# SCH_RGB_LED_stick_th_2022-01-01.net
KiCad netlist of a schematic drawn in EasyEDA
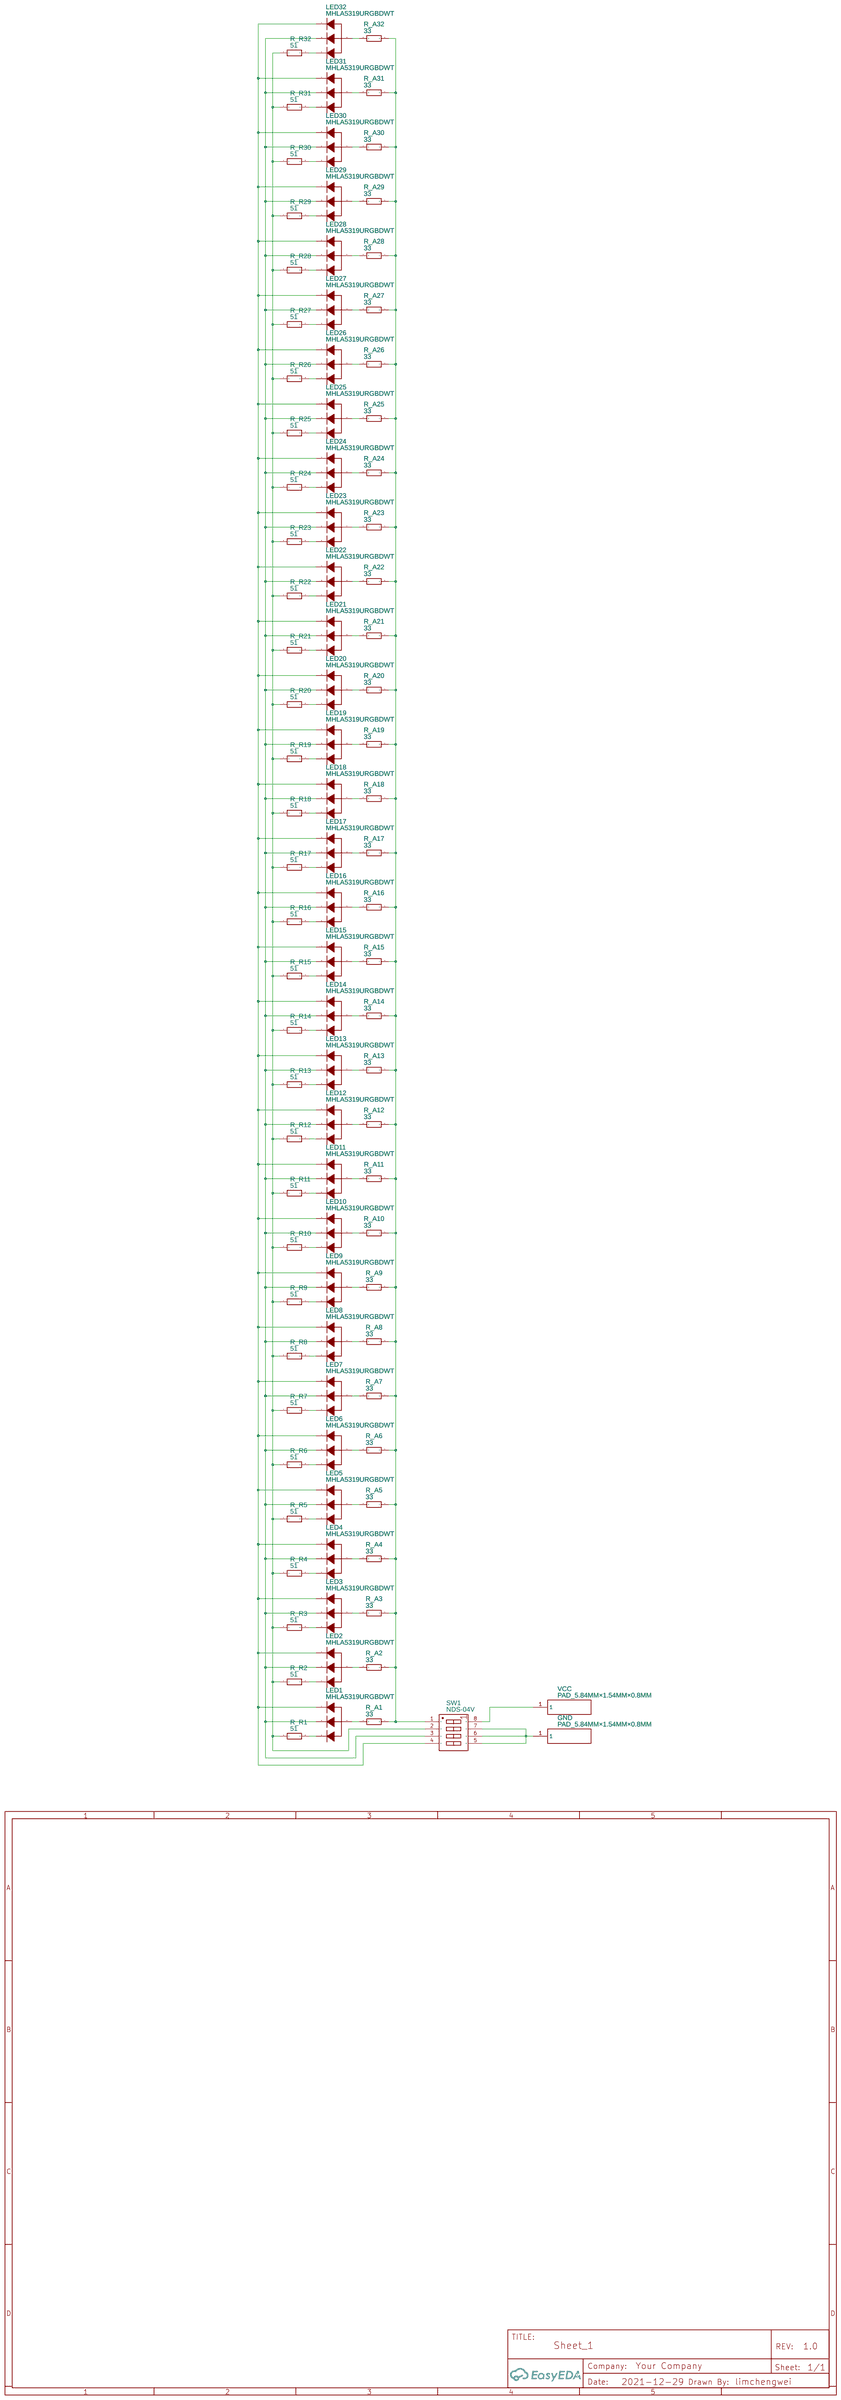
[diagram p0: schematic sheet]

(export (version "E")
  (design (tool "Eeschema 10.0.6"))
  (components
    (comp (ref "GND")
      (value "PAD_5.84MM×1.54MM×0.8MM")
      (fields
        (field (name "BOM_Manufacturer Part") "PAD_5.84mm×1.54mm×0.8mm")
        (field (name "BOM_Supplier Part") "C9900000335")
      )
      (libsource (lib "") (part "PAD_5.84MM×1.54MM×0.8MM"))
    )
    (comp (ref "LED1")
      (value "MHLA5319URGBDWT")
      (fields (field (name "BOM_Supplier Part") "C417349"))
      (libsource (lib "") (part "MHLA5319URGBDWT"))
    )
    (comp (ref "LED2")
      (value "MHLA5319URGBDWT")
      (fields (field (name "BOM_Supplier Part") "C417349"))
      (libsource (lib "") (part "MHLA5319URGBDWT"))
    )
    (comp (ref "LED3")
      (value "MHLA5319URGBDWT")
      (fields (field (name "BOM_Supplier Part") "C417349"))
      (libsource (lib "") (part "MHLA5319URGBDWT"))
    )
    (comp (ref "LED4")
      (value "MHLA5319URGBDWT")
      (fields (field (name "BOM_Supplier Part") "C417349"))
      (libsource (lib "") (part "MHLA5319URGBDWT"))
    )
    (comp (ref "LED5")
      (value "MHLA5319URGBDWT")
      (fields (field (name "BOM_Supplier Part") "C417349"))
      (libsource (lib "") (part "MHLA5319URGBDWT"))
    )
    (comp (ref "LED6")
      (value "MHLA5319URGBDWT")
      (fields (field (name "BOM_Supplier Part") "C417349"))
      (libsource (lib "") (part "MHLA5319URGBDWT"))
    )
    (comp (ref "LED7")
      (value "MHLA5319URGBDWT")
      (fields (field (name "BOM_Supplier Part") "C417349"))
      (libsource (lib "") (part "MHLA5319URGBDWT"))
    )
    (comp (ref "LED8")
      (value "MHLA5319URGBDWT")
      (fields (field (name "BOM_Supplier Part") "C417349"))
      (libsource (lib "") (part "MHLA5319URGBDWT"))
    )
    (comp (ref "LED9")
      (value "MHLA5319URGBDWT")
      (fields (field (name "BOM_Supplier Part") "C417349"))
      (libsource (lib "") (part "MHLA5319URGBDWT"))
    )
    (comp (ref "LED10")
      (value "MHLA5319URGBDWT")
      (fields (field (name "BOM_Supplier Part") "C417349"))
      (libsource (lib "") (part "MHLA5319URGBDWT"))
    )
    (comp (ref "LED11")
      (value "MHLA5319URGBDWT")
      (fields (field (name "BOM_Supplier Part") "C417349"))
      (libsource (lib "") (part "MHLA5319URGBDWT"))
    )
    (comp (ref "LED12")
      (value "MHLA5319URGBDWT")
      (fields (field (name "BOM_Supplier Part") "C417349"))
      (libsource (lib "") (part "MHLA5319URGBDWT"))
    )
    (comp (ref "LED13")
      (value "MHLA5319URGBDWT")
      (fields (field (name "BOM_Supplier Part") "C417349"))
      (libsource (lib "") (part "MHLA5319URGBDWT"))
    )
    (comp (ref "LED14")
      (value "MHLA5319URGBDWT")
      (fields (field (name "BOM_Supplier Part") "C417349"))
      (libsource (lib "") (part "MHLA5319URGBDWT"))
    )
    (comp (ref "LED15")
      (value "MHLA5319URGBDWT")
      (fields (field (name "BOM_Supplier Part") "C417349"))
      (libsource (lib "") (part "MHLA5319URGBDWT"))
    )
    (comp (ref "LED16")
      (value "MHLA5319URGBDWT")
      (fields (field (name "BOM_Supplier Part") "C417349"))
      (libsource (lib "") (part "MHLA5319URGBDWT"))
    )
    (comp (ref "LED17")
      (value "MHLA5319URGBDWT")
      (fields (field (name "BOM_Supplier Part") "C417349"))
      (libsource (lib "") (part "MHLA5319URGBDWT"))
    )
    (comp (ref "LED18")
      (value "MHLA5319URGBDWT")
      (fields (field (name "BOM_Supplier Part") "C417349"))
      (libsource (lib "") (part "MHLA5319URGBDWT"))
    )
    (comp (ref "LED19")
      (value "MHLA5319URGBDWT")
      (fields (field (name "BOM_Supplier Part") "C417349"))
      (libsource (lib "") (part "MHLA5319URGBDWT"))
    )
    (comp (ref "LED20")
      (value "MHLA5319URGBDWT")
      (fields (field (name "BOM_Supplier Part") "C417349"))
      (libsource (lib "") (part "MHLA5319URGBDWT"))
    )
    (comp (ref "LED21")
      (value "MHLA5319URGBDWT")
      (fields (field (name "BOM_Supplier Part") "C417349"))
      (libsource (lib "") (part "MHLA5319URGBDWT"))
    )
    (comp (ref "LED22")
      (value "MHLA5319URGBDWT")
      (fields (field (name "BOM_Supplier Part") "C417349"))
      (libsource (lib "") (part "MHLA5319URGBDWT"))
    )
    (comp (ref "LED23")
      (value "MHLA5319URGBDWT")
      (fields (field (name "BOM_Supplier Part") "C417349"))
      (libsource (lib "") (part "MHLA5319URGBDWT"))
    )
    (comp (ref "LED24")
      (value "MHLA5319URGBDWT")
      (fields (field (name "BOM_Supplier Part") "C417349"))
      (libsource (lib "") (part "MHLA5319URGBDWT"))
    )
    (comp (ref "LED25")
      (value "MHLA5319URGBDWT")
      (fields (field (name "BOM_Supplier Part") "C417349"))
      (libsource (lib "") (part "MHLA5319URGBDWT"))
    )
    (comp (ref "LED26")
      (value "MHLA5319URGBDWT")
      (fields (field (name "BOM_Supplier Part") "C417349"))
      (libsource (lib "") (part "MHLA5319URGBDWT"))
    )
    (comp (ref "LED27")
      (value "MHLA5319URGBDWT")
      (fields (field (name "BOM_Supplier Part") "C417349"))
      (libsource (lib "") (part "MHLA5319URGBDWT"))
    )
    (comp (ref "LED28")
      (value "MHLA5319URGBDWT")
      (fields (field (name "BOM_Supplier Part") "C417349"))
      (libsource (lib "") (part "MHLA5319URGBDWT"))
    )
    (comp (ref "LED29")
      (value "MHLA5319URGBDWT")
      (fields (field (name "BOM_Supplier Part") "C417349"))
      (libsource (lib "") (part "MHLA5319URGBDWT"))
    )
    (comp (ref "LED30")
      (value "MHLA5319URGBDWT")
      (fields (field (name "BOM_Supplier Part") "C417349"))
      (libsource (lib "") (part "MHLA5319URGBDWT"))
    )
    (comp (ref "LED31")
      (value "MHLA5319URGBDWT")
      (fields (field (name "BOM_Supplier Part") "C417349"))
      (libsource (lib "") (part "MHLA5319URGBDWT"))
    )
    (comp (ref "LED32")
      (value "MHLA5319URGBDWT")
      (fields (field (name "BOM_Supplier Part") "C417349"))
      (libsource (lib "") (part "MHLA5319URGBDWT"))
    )
    (comp (ref "R_A1")
      (value "33")
      (fields (field (name "BOM_Supplier Part") "C119319"))
      (libsource (lib "") (part "MF1/4W-620Ω±1% T52_1"))
    )
    (comp (ref "R_A2")
      (value "33")
      (fields (field (name "BOM_Supplier Part") "C119319"))
      (libsource (lib "") (part "MF1/4W-620Ω±1% T52_1"))
    )
    (comp (ref "R_A3")
      (value "33")
      (fields (field (name "BOM_Supplier Part") "C119319"))
      (libsource (lib "") (part "MF1/4W-620Ω±1% T52_1"))
    )
    (comp (ref "R_A4")
      (value "33")
      (fields (field (name "BOM_Supplier Part") "C119319"))
      (libsource (lib "") (part "MF1/4W-620Ω±1% T52_1"))
    )
    (comp (ref "R_A5")
      (value "33")
      (fields (field (name "BOM_Supplier Part") "C119319"))
      (libsource (lib "") (part "MF1/4W-620Ω±1% T52_1"))
    )
    (comp (ref "R_A6")
      (value "33")
      (fields (field (name "BOM_Supplier Part") "C119319"))
      (libsource (lib "") (part "MF1/4W-620Ω±1% T52_1"))
    )
    (comp (ref "R_A7")
      (value "33")
      (fields (field (name "BOM_Supplier Part") "C119319"))
      (libsource (lib "") (part "MF1/4W-620Ω±1% T52_1"))
    )
    (comp (ref "R_A8")
      (value "33")
      (fields (field (name "BOM_Supplier Part") "C119319"))
      (libsource (lib "") (part "MF1/4W-620Ω±1% T52_1"))
    )
    (comp (ref "R_A9")
      (value "33")
      (fields (field (name "BOM_Supplier Part") "C119319"))
      (libsource (lib "") (part "MF1/4W-620Ω±1% T52_1"))
    )
    (comp (ref "R_A10")
      (value "33")
      (fields (field (name "BOM_Supplier Part") "C119319"))
      (libsource (lib "") (part "MF1/4W-620Ω±1% T52_1"))
    )
    (comp (ref "R_A11")
      (value "33")
      (fields (field (name "BOM_Supplier Part") "C119319"))
      (libsource (lib "") (part "MF1/4W-620Ω±1% T52_1"))
    )
    (comp (ref "R_A12")
      (value "33")
      (fields (field (name "BOM_Supplier Part") "C119319"))
      (libsource (lib "") (part "MF1/4W-620Ω±1% T52_1"))
    )
    (comp (ref "R_A13")
      (value "33")
      (fields (field (name "BOM_Supplier Part") "C119319"))
      (libsource (lib "") (part "MF1/4W-620Ω±1% T52_1"))
    )
    (comp (ref "R_A14")
      (value "33")
      (fields (field (name "BOM_Supplier Part") "C119319"))
      (libsource (lib "") (part "MF1/4W-620Ω±1% T52_1"))
    )
    (comp (ref "R_A15")
      (value "33")
      (fields (field (name "BOM_Supplier Part") "C119319"))
      (libsource (lib "") (part "MF1/4W-620Ω±1% T52_1"))
    )
    (comp (ref "R_A16")
      (value "33")
      (fields (field (name "BOM_Supplier Part") "C119319"))
      (libsource (lib "") (part "MF1/4W-620Ω±1% T52_1"))
    )
    (comp (ref "R_A17")
      (value "33")
      (fields (field (name "BOM_Supplier Part") "C119319"))
      (libsource (lib "") (part "MF1/4W-620Ω±1% T52_1"))
    )
    (comp (ref "R_A18")
      (value "33")
      (fields (field (name "BOM_Supplier Part") "C119319"))
      (libsource (lib "") (part "MF1/4W-620Ω±1% T52_1"))
    )
    (comp (ref "R_A19")
      (value "33")
      (fields (field (name "BOM_Supplier Part") "C119319"))
      (libsource (lib "") (part "MF1/4W-620Ω±1% T52_1"))
    )
    (comp (ref "R_A20")
      (value "33")
      (fields (field (name "BOM_Supplier Part") "C119319"))
      (libsource (lib "") (part "MF1/4W-620Ω±1% T52_1"))
    )
    (comp (ref "R_A21")
      (value "33")
      (fields (field (name "BOM_Supplier Part") "C119319"))
      (libsource (lib "") (part "MF1/4W-620Ω±1% T52_1"))
    )
    (comp (ref "R_A22")
      (value "33")
      (fields (field (name "BOM_Supplier Part") "C119319"))
      (libsource (lib "") (part "MF1/4W-620Ω±1% T52_1"))
    )
    (comp (ref "R_A23")
      (value "33")
      (fields (field (name "BOM_Supplier Part") "C119319"))
      (libsource (lib "") (part "MF1/4W-620Ω±1% T52_1"))
    )
    (comp (ref "R_A24")
      (value "33")
      (fields (field (name "BOM_Supplier Part") "C119319"))
      (libsource (lib "") (part "MF1/4W-620Ω±1% T52_1"))
    )
    (comp (ref "R_A25")
      (value "33")
      (fields (field (name "BOM_Supplier Part") "C119319"))
      (libsource (lib "") (part "MF1/4W-620Ω±1% T52_1"))
    )
    (comp (ref "R_A26")
      (value "33")
      (fields (field (name "BOM_Supplier Part") "C119319"))
      (libsource (lib "") (part "MF1/4W-620Ω±1% T52_1"))
    )
    (comp (ref "R_A27")
      (value "33")
      (fields (field (name "BOM_Supplier Part") "C119319"))
      (libsource (lib "") (part "MF1/4W-620Ω±1% T52_1"))
    )
    (comp (ref "R_A28")
      (value "33")
      (fields (field (name "BOM_Supplier Part") "C119319"))
      (libsource (lib "") (part "MF1/4W-620Ω±1% T52_1"))
    )
    (comp (ref "R_A29")
      (value "33")
      (fields (field (name "BOM_Supplier Part") "C119319"))
      (libsource (lib "") (part "MF1/4W-620Ω±1% T52_1"))
    )
    (comp (ref "R_A30")
      (value "33")
      (fields (field (name "BOM_Supplier Part") "C119319"))
      (libsource (lib "") (part "MF1/4W-620Ω±1% T52_1"))
    )
    (comp (ref "R_A31")
      (value "33")
      (fields (field (name "BOM_Supplier Part") "C119319"))
      (libsource (lib "") (part "MF1/4W-620Ω±1% T52_1"))
    )
    (comp (ref "R_A32")
      (value "33")
      (fields (field (name "BOM_Supplier Part") "C119319"))
      (libsource (lib "") (part "MF1/4W-620Ω±1% T52_1"))
    )
    (comp (ref "R_R1")
      (value "51")
      (fields (field (name "BOM_Supplier Part") "C119319"))
      (libsource (lib "") (part "MF1/4W-620Ω±1% T52"))
    )
    (comp (ref "R_R2")
      (value "51")
      (fields (field (name "BOM_Supplier Part") "C119319"))
      (libsource (lib "") (part "MF1/4W-620Ω±1% T52"))
    )
    (comp (ref "R_R3")
      (value "51")
      (fields (field (name "BOM_Supplier Part") "C119319"))
      (libsource (lib "") (part "MF1/4W-620Ω±1% T52"))
    )
    (comp (ref "R_R4")
      (value "51")
      (fields (field (name "BOM_Supplier Part") "C119319"))
      (libsource (lib "") (part "MF1/4W-620Ω±1% T52"))
    )
    (comp (ref "R_R5")
      (value "51")
      (fields (field (name "BOM_Supplier Part") "C119319"))
      (libsource (lib "") (part "MF1/4W-620Ω±1% T52"))
    )
    (comp (ref "R_R6")
      (value "51")
      (fields (field (name "BOM_Supplier Part") "C119319"))
      (libsource (lib "") (part "MF1/4W-620Ω±1% T52"))
    )
    (comp (ref "R_R7")
      (value "51")
      (fields (field (name "BOM_Supplier Part") "C119319"))
      (libsource (lib "") (part "MF1/4W-620Ω±1% T52"))
    )
    (comp (ref "R_R8")
      (value "51")
      (fields (field (name "BOM_Supplier Part") "C119319"))
      (libsource (lib "") (part "MF1/4W-620Ω±1% T52"))
    )
    (comp (ref "R_R9")
      (value "51")
      (fields (field (name "BOM_Supplier Part") "C119319"))
      (libsource (lib "") (part "MF1/4W-620Ω±1% T52"))
    )
    (comp (ref "R_R10")
      (value "51")
      (fields (field (name "BOM_Supplier Part") "C119319"))
      (libsource (lib "") (part "MF1/4W-620Ω±1% T52"))
    )
    (comp (ref "R_R11")
      (value "51")
      (fields (field (name "BOM_Supplier Part") "C119319"))
      (libsource (lib "") (part "MF1/4W-620Ω±1% T52"))
    )
    (comp (ref "R_R12")
      (value "51")
      (fields (field (name "BOM_Supplier Part") "C119319"))
      (libsource (lib "") (part "MF1/4W-620Ω±1% T52"))
    )
    (comp (ref "R_R13")
      (value "51")
      (fields (field (name "BOM_Supplier Part") "C119319"))
      (libsource (lib "") (part "MF1/4W-620Ω±1% T52"))
    )
    (comp (ref "R_R14")
      (value "51")
      (fields (field (name "BOM_Supplier Part") "C119319"))
      (libsource (lib "") (part "MF1/4W-620Ω±1% T52"))
    )
    (comp (ref "R_R15")
      (value "51")
      (fields (field (name "BOM_Supplier Part") "C119319"))
      (libsource (lib "") (part "MF1/4W-620Ω±1% T52"))
    )
    (comp (ref "R_R16")
      (value "51")
      (fields (field (name "BOM_Supplier Part") "C119319"))
      (libsource (lib "") (part "MF1/4W-620Ω±1% T52"))
    )
    (comp (ref "R_R17")
      (value "51")
      (fields (field (name "BOM_Supplier Part") "C119319"))
      (libsource (lib "") (part "MF1/4W-620Ω±1% T52"))
    )
    (comp (ref "R_R18")
      (value "51")
      (fields (field (name "BOM_Supplier Part") "C119319"))
      (libsource (lib "") (part "MF1/4W-620Ω±1% T52"))
    )
    (comp (ref "R_R19")
      (value "51")
      (fields (field (name "BOM_Supplier Part") "C119319"))
      (libsource (lib "") (part "MF1/4W-620Ω±1% T52"))
    )
    (comp (ref "R_R20")
      (value "51")
      (fields (field (name "BOM_Supplier Part") "C119319"))
      (libsource (lib "") (part "MF1/4W-620Ω±1% T52"))
    )
    (comp (ref "R_R21")
      (value "51")
      (fields (field (name "BOM_Supplier Part") "C119319"))
      (libsource (lib "") (part "MF1/4W-620Ω±1% T52"))
    )
    (comp (ref "R_R22")
      (value "51")
      (fields (field (name "BOM_Supplier Part") "C119319"))
      (libsource (lib "") (part "MF1/4W-620Ω±1% T52"))
    )
    (comp (ref "R_R23")
      (value "51")
      (fields (field (name "BOM_Supplier Part") "C119319"))
      (libsource (lib "") (part "MF1/4W-620Ω±1% T52"))
    )
    (comp (ref "R_R24")
      (value "51")
      (fields (field (name "BOM_Supplier Part") "C119319"))
      (libsource (lib "") (part "MF1/4W-620Ω±1% T52"))
    )
    (comp (ref "R_R25")
      (value "51")
      (fields (field (name "BOM_Supplier Part") "C119319"))
      (libsource (lib "") (part "MF1/4W-620Ω±1% T52"))
    )
    (comp (ref "R_R26")
      (value "51")
      (fields (field (name "BOM_Supplier Part") "C119319"))
      (libsource (lib "") (part "MF1/4W-620Ω±1% T52"))
    )
    (comp (ref "R_R27")
      (value "51")
      (fields (field (name "BOM_Supplier Part") "C119319"))
      (libsource (lib "") (part "MF1/4W-620Ω±1% T52"))
    )
    (comp (ref "R_R28")
      (value "51")
      (fields (field (name "BOM_Supplier Part") "C119319"))
      (libsource (lib "") (part "MF1/4W-620Ω±1% T52"))
    )
    (comp (ref "R_R29")
      (value "51")
      (fields (field (name "BOM_Supplier Part") "C119319"))
      (libsource (lib "") (part "MF1/4W-620Ω±1% T52"))
    )
    (comp (ref "R_R30")
      (value "51")
      (fields (field (name "BOM_Supplier Part") "C119319"))
      (libsource (lib "") (part "MF1/4W-620Ω±1% T52"))
    )
    (comp (ref "R_R31")
      (value "51")
      (fields (field (name "BOM_Supplier Part") "C119319"))
      (libsource (lib "") (part "MF1/4W-620Ω±1% T52"))
    )
    (comp (ref "R_R32")
      (value "51")
      (fields (field (name "BOM_Supplier Part") "C119319"))
      (libsource (lib "") (part "MF1/4W-620Ω±1% T52"))
    )
    (comp (ref "SW1")
      (value "NDS-04V")
      (fields (field (name "BOM_Supplier Part") "C501536"))
      (libsource (lib "") (part "NDS-04V"))
    )
    (comp (ref "VCC")
      (value "PAD_5.84MM×1.54MM×0.8MM")
      (fields
        (field (name "BOM_Manufacturer Part") "PAD_5.84mm×1.54mm×0.8mm")
        (field (name "BOM_Supplier Part") "C9900000335")
      )
      (libsource (lib "") (part "PAD_5.84MM×1.54MM×0.8MM_1"))
    )
  )
  (nets
    (net (code "1") (name "Net-(LED1-+)") (class "Default")
      (node (ref "LED1") (pin "2") (pinfunction "+_2") (pintype "unspecified"))
      (node (ref "R_A1") (pin "2") (pinfunction "2_2") (pintype "unspecified"))
    )
    (net (code "2") (name "Net-(LED1---Pad1)") (class "Default")
      (node (ref "LED1") (pin "1") (pinfunction "-_1") (pintype "unspecified"))
      (node (ref "R_R1") (pin "2") (pinfunction "2_2") (pintype "unspecified"))
    )
    (net (code "3") (name "Net-(LED2-+)") (class "Default")
      (node (ref "LED2") (pin "2") (pinfunction "+_2") (pintype "unspecified"))
      (node (ref "R_A2") (pin "2") (pinfunction "2_2") (pintype "unspecified"))
    )
    (net (code "4") (name "Net-(LED2---Pad1)") (class "Default")
      (node (ref "LED2") (pin "1") (pinfunction "-_1") (pintype "unspecified"))
      (node (ref "R_R2") (pin "2") (pinfunction "2_2") (pintype "unspecified"))
    )
    (net (code "5") (name "Net-(LED3-+)") (class "Default")
      (node (ref "LED3") (pin "2") (pinfunction "+_2") (pintype "unspecified"))
      (node (ref "R_A3") (pin "2") (pinfunction "2_2") (pintype "unspecified"))
    )
    (net (code "6") (name "Net-(LED3---Pad1)") (class "Default")
      (node (ref "LED3") (pin "1") (pinfunction "-_1") (pintype "unspecified"))
      (node (ref "R_R3") (pin "2") (pinfunction "2_2") (pintype "unspecified"))
    )
    (net (code "7") (name "Net-(LED4-+)") (class "Default")
      (node (ref "LED4") (pin "2") (pinfunction "+_2") (pintype "unspecified"))
      (node (ref "R_A4") (pin "2") (pinfunction "2_2") (pintype "unspecified"))
    )
    (net (code "8") (name "Net-(LED4---Pad1)") (class "Default")
      (node (ref "LED4") (pin "1") (pinfunction "-_1") (pintype "unspecified"))
      (node (ref "R_R4") (pin "2") (pinfunction "2_2") (pintype "unspecified"))
    )
    (net (code "9") (name "Net-(LED5-+)") (class "Default")
      (node (ref "LED5") (pin "2") (pinfunction "+_2") (pintype "unspecified"))
      (node (ref "R_A5") (pin "2") (pinfunction "2_2") (pintype "unspecified"))
    )
    (net (code "10") (name "Net-(LED5---Pad1)") (class "Default")
      (node (ref "LED5") (pin "1") (pinfunction "-_1") (pintype "unspecified"))
      (node (ref "R_R5") (pin "2") (pinfunction "2_2") (pintype "unspecified"))
    )
    (net (code "11") (name "Net-(LED6-+)") (class "Default")
      (node (ref "LED6") (pin "2") (pinfunction "+_2") (pintype "unspecified"))
      (node (ref "R_A6") (pin "2") (pinfunction "2_2") (pintype "unspecified"))
    )
    (net (code "12") (name "Net-(LED6---Pad1)") (class "Default")
      (node (ref "LED6") (pin "1") (pinfunction "-_1") (pintype "unspecified"))
      (node (ref "R_R6") (pin "2") (pinfunction "2_2") (pintype "unspecified"))
    )
    (net (code "13") (name "Net-(LED7-+)") (class "Default")
      (node (ref "LED7") (pin "2") (pinfunction "+_2") (pintype "unspecified"))
      (node (ref "R_A7") (pin "2") (pinfunction "2_2") (pintype "unspecified"))
    )
    (net (code "14") (name "Net-(LED7---Pad1)") (class "Default")
      (node (ref "LED7") (pin "1") (pinfunction "-_1") (pintype "unspecified"))
      (node (ref "R_R7") (pin "2") (pinfunction "2_2") (pintype "unspecified"))
    )
    (net (code "15") (name "Net-(LED8-+)") (class "Default")
      (node (ref "LED8") (pin "2") (pinfunction "+_2") (pintype "unspecified"))
      (node (ref "R_A8") (pin "2") (pinfunction "2_2") (pintype "unspecified"))
    )
    (net (code "16") (name "Net-(LED8---Pad1)") (class "Default")
      (node (ref "LED8") (pin "1") (pinfunction "-_1") (pintype "unspecified"))
      (node (ref "R_R8") (pin "2") (pinfunction "2_2") (pintype "unspecified"))
    )
    (net (code "17") (name "Net-(LED9-+)") (class "Default")
      (node (ref "LED9") (pin "2") (pinfunction "+_2") (pintype "unspecified"))
      (node (ref "R_A9") (pin "2") (pinfunction "2_2") (pintype "unspecified"))
    )
    (net (code "18") (name "Net-(LED9---Pad1)") (class "Default")
      (node (ref "LED9") (pin "1") (pinfunction "-_1") (pintype "unspecified"))
      (node (ref "R_R9") (pin "2") (pinfunction "2_2") (pintype "unspecified"))
    )
    (net (code "19") (name "Net-(LED10-+)") (class "Default")
      (node (ref "LED10") (pin "2") (pinfunction "+_2") (pintype "unspecified"))
      (node (ref "R_A10") (pin "2") (pinfunction "2_2") (pintype "unspecified"))
    )
    (net (code "20") (name "Net-(LED10---Pad1)") (class "Default")
      (node (ref "LED10") (pin "1") (pinfunction "-_1") (pintype "unspecified"))
      (node (ref "R_R10") (pin "2") (pinfunction "2_2") (pintype "unspecified"))
    )
    (net (code "21") (name "Net-(LED11-+)") (class "Default")
      (node (ref "LED11") (pin "2") (pinfunction "+_2") (pintype "unspecified"))
      (node (ref "R_A11") (pin "2") (pinfunction "2_2") (pintype "unspecified"))
    )
    (net (code "22") (name "Net-(LED11---Pad1)") (class "Default")
      (node (ref "LED11") (pin "1") (pinfunction "-_1") (pintype "unspecified"))
      (node (ref "R_R11") (pin "2") (pinfunction "2_2") (pintype "unspecified"))
    )
    (net (code "23") (name "Net-(LED12-+)") (class "Default")
      (node (ref "LED12") (pin "2") (pinfunction "+_2") (pintype "unspecified"))
      (node (ref "R_A12") (pin "2") (pinfunction "2_2") (pintype "unspecified"))
    )
    (net (code "24") (name "Net-(LED12---Pad1)") (class "Default")
      (node (ref "LED12") (pin "1") (pinfunction "-_1") (pintype "unspecified"))
      (node (ref "R_R12") (pin "2") (pinfunction "2_2") (pintype "unspecified"))
    )
    (net (code "25") (name "Net-(LED13-+)") (class "Default")
      (node (ref "LED13") (pin "2") (pinfunction "+_2") (pintype "unspecified"))
      (node (ref "R_A13") (pin "2") (pinfunction "2_2") (pintype "unspecified"))
    )
    (net (code "26") (name "Net-(LED13---Pad1)") (class "Default")
      (node (ref "LED13") (pin "1") (pinfunction "-_1") (pintype "unspecified"))
      (node (ref "R_R13") (pin "2") (pinfunction "2_2") (pintype "unspecified"))
    )
    (net (code "27") (name "Net-(LED14-+)") (class "Default")
      (node (ref "LED14") (pin "2") (pinfunction "+_2") (pintype "unspecified"))
      (node (ref "R_A14") (pin "2") (pinfunction "2_2") (pintype "unspecified"))
    )
    (net (code "28") (name "Net-(LED14---Pad1)") (class "Default")
      (node (ref "LED14") (pin "1") (pinfunction "-_1") (pintype "unspecified"))
      (node (ref "R_R14") (pin "2") (pinfunction "2_2") (pintype "unspecified"))
    )
    (net (code "29") (name "Net-(LED15-+)") (class "Default")
      (node (ref "LED15") (pin "2") (pinfunction "+_2") (pintype "unspecified"))
      (node (ref "R_A15") (pin "2") (pinfunction "2_2") (pintype "unspecified"))
    )
    (net (code "30") (name "Net-(LED15---Pad1)") (class "Default")
      (node (ref "LED15") (pin "1") (pinfunction "-_1") (pintype "unspecified"))
      (node (ref "R_R15") (pin "2") (pinfunction "2_2") (pintype "unspecified"))
    )
    (net (code "31") (name "Net-(LED16-+)") (class "Default")
      (node (ref "LED16") (pin "2") (pinfunction "+_2") (pintype "unspecified"))
      (node (ref "R_A16") (pin "2") (pinfunction "2_2") (pintype "unspecified"))
    )
    (net (code "32") (name "Net-(LED16---Pad1)") (class "Default")
      (node (ref "LED16") (pin "1") (pinfunction "-_1") (pintype "unspecified"))
      (node (ref "R_R16") (pin "2") (pinfunction "2_2") (pintype "unspecified"))
    )
    (net (code "33") (name "Net-(LED17-+)") (class "Default")
      (node (ref "LED17") (pin "2") (pinfunction "+_2") (pintype "unspecified"))
      (node (ref "R_A17") (pin "2") (pinfunction "2_2") (pintype "unspecified"))
    )
    (net (code "34") (name "Net-(LED17---Pad1)") (class "Default")
      (node (ref "LED17") (pin "1") (pinfunction "-_1") (pintype "unspecified"))
      (node (ref "R_R17") (pin "2") (pinfunction "2_2") (pintype "unspecified"))
    )
    (net (code "35") (name "Net-(LED18-+)") (class "Default")
      (node (ref "LED18") (pin "2") (pinfunction "+_2") (pintype "unspecified"))
      (node (ref "R_A18") (pin "2") (pinfunction "2_2") (pintype "unspecified"))
    )
    (net (code "36") (name "Net-(LED18---Pad1)") (class "Default")
      (node (ref "LED18") (pin "1") (pinfunction "-_1") (pintype "unspecified"))
      (node (ref "R_R18") (pin "2") (pinfunction "2_2") (pintype "unspecified"))
    )
    (net (code "37") (name "Net-(LED19-+)") (class "Default")
      (node (ref "LED19") (pin "2") (pinfunction "+_2") (pintype "unspecified"))
      (node (ref "R_A19") (pin "2") (pinfunction "2_2") (pintype "unspecified"))
    )
    (net (code "38") (name "Net-(LED19---Pad1)") (class "Default")
      (node (ref "LED19") (pin "1") (pinfunction "-_1") (pintype "unspecified"))
      (node (ref "R_R19") (pin "2") (pinfunction "2_2") (pintype "unspecified"))
    )
    (net (code "39") (name "Net-(LED20-+)") (class "Default")
      (node (ref "LED20") (pin "2") (pinfunction "+_2") (pintype "unspecified"))
      (node (ref "R_A20") (pin "2") (pinfunction "2_2") (pintype "unspecified"))
    )
    (net (code "40") (name "Net-(LED20---Pad1)") (class "Default")
      (node (ref "LED20") (pin "1") (pinfunction "-_1") (pintype "unspecified"))
      (node (ref "R_R20") (pin "2") (pinfunction "2_2") (pintype "unspecified"))
    )
    (net (code "41") (name "Net-(LED21-+)") (class "Default")
      (node (ref "LED21") (pin "2") (pinfunction "+_2") (pintype "unspecified"))
      (node (ref "R_A21") (pin "2") (pinfunction "2_2") (pintype "unspecified"))
    )
    (net (code "42") (name "Net-(LED21---Pad1)") (class "Default")
      (node (ref "LED21") (pin "1") (pinfunction "-_1") (pintype "unspecified"))
      (node (ref "R_R21") (pin "2") (pinfunction "2_2") (pintype "unspecified"))
    )
    (net (code "43") (name "Net-(LED22-+)") (class "Default")
      (node (ref "LED22") (pin "2") (pinfunction "+_2") (pintype "unspecified"))
      (node (ref "R_A22") (pin "2") (pinfunction "2_2") (pintype "unspecified"))
    )
    (net (code "44") (name "Net-(LED22---Pad1)") (class "Default")
      (node (ref "LED22") (pin "1") (pinfunction "-_1") (pintype "unspecified"))
      (node (ref "R_R22") (pin "2") (pinfunction "2_2") (pintype "unspecified"))
    )
    (net (code "45") (name "Net-(LED23-+)") (class "Default")
      (node (ref "LED23") (pin "2") (pinfunction "+_2") (pintype "unspecified"))
      (node (ref "R_A23") (pin "2") (pinfunction "2_2") (pintype "unspecified"))
    )
    (net (code "46") (name "Net-(LED23---Pad1)") (class "Default")
      (node (ref "LED23") (pin "1") (pinfunction "-_1") (pintype "unspecified"))
      (node (ref "R_R23") (pin "2") (pinfunction "2_2") (pintype "unspecified"))
    )
    (net (code "47") (name "Net-(LED24-+)") (class "Default")
      (node (ref "LED24") (pin "2") (pinfunction "+_2") (pintype "unspecified"))
      (node (ref "R_A24") (pin "2") (pinfunction "2_2") (pintype "unspecified"))
    )
    (net (code "48") (name "Net-(LED24---Pad1)") (class "Default")
      (node (ref "LED24") (pin "1") (pinfunction "-_1") (pintype "unspecified"))
      (node (ref "R_R24") (pin "2") (pinfunction "2_2") (pintype "unspecified"))
    )
    (net (code "49") (name "Net-(LED25-+)") (class "Default")
      (node (ref "LED25") (pin "2") (pinfunction "+_2") (pintype "unspecified"))
      (node (ref "R_A25") (pin "2") (pinfunction "2_2") (pintype "unspecified"))
    )
    (net (code "50") (name "Net-(LED25---Pad1)") (class "Default")
      (node (ref "LED25") (pin "1") (pinfunction "-_1") (pintype "unspecified"))
      (node (ref "R_R25") (pin "2") (pinfunction "2_2") (pintype "unspecified"))
    )
    (net (code "51") (name "Net-(LED26-+)") (class "Default")
      (node (ref "LED26") (pin "2") (pinfunction "+_2") (pintype "unspecified"))
      (node (ref "R_A26") (pin "2") (pinfunction "2_2") (pintype "unspecified"))
    )
    (net (code "52") (name "Net-(LED26---Pad1)") (class "Default")
      (node (ref "LED26") (pin "1") (pinfunction "-_1") (pintype "unspecified"))
      (node (ref "R_R26") (pin "2") (pinfunction "2_2") (pintype "unspecified"))
    )
    (net (code "53") (name "Net-(LED27-+)") (class "Default")
      (node (ref "LED27") (pin "2") (pinfunction "+_2") (pintype "unspecified"))
      (node (ref "R_A27") (pin "2") (pinfunction "2_2") (pintype "unspecified"))
    )
    (net (code "54") (name "Net-(LED27---Pad1)") (class "Default")
      (node (ref "LED27") (pin "1") (pinfunction "-_1") (pintype "unspecified"))
      (node (ref "R_R27") (pin "2") (pinfunction "2_2") (pintype "unspecified"))
    )
    (net (code "55") (name "Net-(LED28-+)") (class "Default")
      (node (ref "LED28") (pin "2") (pinfunction "+_2") (pintype "unspecified"))
      (node (ref "R_A28") (pin "2") (pinfunction "2_2") (pintype "unspecified"))
    )
    (net (code "56") (name "Net-(LED28---Pad1)") (class "Default")
      (node (ref "LED28") (pin "1") (pinfunction "-_1") (pintype "unspecified"))
      (node (ref "R_R28") (pin "2") (pinfunction "2_2") (pintype "unspecified"))
    )
    (net (code "57") (name "Net-(LED29-+)") (class "Default")
      (node (ref "LED29") (pin "2") (pinfunction "+_2") (pintype "unspecified"))
      (node (ref "R_A29") (pin "2") (pinfunction "2_2") (pintype "unspecified"))
    )
    (net (code "58") (name "Net-(LED29---Pad1)") (class "Default")
      (node (ref "LED29") (pin "1") (pinfunction "-_1") (pintype "unspecified"))
      (node (ref "R_R29") (pin "2") (pinfunction "2_2") (pintype "unspecified"))
    )
    (net (code "59") (name "Net-(LED30-+)") (class "Default")
      (node (ref "LED30") (pin "2") (pinfunction "+_2") (pintype "unspecified"))
      (node (ref "R_A30") (pin "2") (pinfunction "2_2") (pintype "unspecified"))
    )
    (net (code "60") (name "Net-(LED30---Pad1)") (class "Default")
      (node (ref "LED30") (pin "1") (pinfunction "-_1") (pintype "unspecified"))
      (node (ref "R_R30") (pin "2") (pinfunction "2_2") (pintype "unspecified"))
    )
    (net (code "61") (name "Net-(LED31-+)") (class "Default")
      (node (ref "LED31") (pin "2") (pinfunction "+_2") (pintype "unspecified"))
      (node (ref "R_A31") (pin "2") (pinfunction "2_2") (pintype "unspecified"))
    )
    (net (code "62") (name "Net-(LED31---Pad1)") (class "Default")
      (node (ref "LED31") (pin "1") (pinfunction "-_1") (pintype "unspecified"))
      (node (ref "R_R31") (pin "2") (pinfunction "2_2") (pintype "unspecified"))
    )
    (net (code "63") (name "Net-(LED32-+)") (class "Default")
      (node (ref "LED32") (pin "2") (pinfunction "+_2") (pintype "unspecified"))
      (node (ref "R_A32") (pin "2") (pinfunction "2_2") (pintype "unspecified"))
    )
    (net (code "64") (name "Net-(LED32---Pad1)") (class "Default")
      (node (ref "LED32") (pin "1") (pinfunction "-_1") (pintype "unspecified"))
      (node (ref "R_R32") (pin "2") (pinfunction "2_2") (pintype "unspecified"))
    )
    (net (code "65") (name "Net-(SW1-PIN1)") (class "Default")
      (node (ref "R_A1") (pin "1") (pinfunction "1_1") (pintype "unspecified"))
      (node (ref "R_A10") (pin "1") (pinfunction "1_1") (pintype "unspecified"))
      (node (ref "R_A11") (pin "1") (pinfunction "1_1") (pintype "unspecified"))
      (node (ref "R_A12") (pin "1") (pinfunction "1_1") (pintype "unspecified"))
      (node (ref "R_A13") (pin "1") (pinfunction "1_1") (pintype "unspecified"))
      (node (ref "R_A14") (pin "1") (pinfunction "1_1") (pintype "unspecified"))
      (node (ref "R_A15") (pin "1") (pinfunction "1_1") (pintype "unspecified"))
      (node (ref "R_A16") (pin "1") (pinfunction "1_1") (pintype "unspecified"))
      (node (ref "R_A17") (pin "1") (pinfunction "1_1") (pintype "unspecified"))
      (node (ref "R_A18") (pin "1") (pinfunction "1_1") (pintype "unspecified"))
      (node (ref "R_A19") (pin "1") (pinfunction "1_1") (pintype "unspecified"))
      (node (ref "R_A2") (pin "1") (pinfunction "1_1") (pintype "unspecified"))
      (node (ref "R_A20") (pin "1") (pinfunction "1_1") (pintype "unspecified"))
      (node (ref "R_A21") (pin "1") (pinfunction "1_1") (pintype "unspecified"))
      (node (ref "R_A22") (pin "1") (pinfunction "1_1") (pintype "unspecified"))
      (node (ref "R_A23") (pin "1") (pinfunction "1_1") (pintype "unspecified"))
      (node (ref "R_A24") (pin "1") (pinfunction "1_1") (pintype "unspecified"))
      (node (ref "R_A25") (pin "1") (pinfunction "1_1") (pintype "unspecified"))
      (node (ref "R_A26") (pin "1") (pinfunction "1_1") (pintype "unspecified"))
      (node (ref "R_A27") (pin "1") (pinfunction "1_1") (pintype "unspecified"))
      (node (ref "R_A28") (pin "1") (pinfunction "1_1") (pintype "unspecified"))
      (node (ref "R_A29") (pin "1") (pinfunction "1_1") (pintype "unspecified"))
      (node (ref "R_A3") (pin "1") (pinfunction "1_1") (pintype "unspecified"))
      (node (ref "R_A30") (pin "1") (pinfunction "1_1") (pintype "unspecified"))
      (node (ref "R_A31") (pin "1") (pinfunction "1_1") (pintype "unspecified"))
      (node (ref "R_A32") (pin "1") (pinfunction "1_1") (pintype "unspecified"))
      (node (ref "R_A4") (pin "1") (pinfunction "1_1") (pintype "unspecified"))
      (node (ref "R_A5") (pin "1") (pinfunction "1_1") (pintype "unspecified"))
      (node (ref "R_A6") (pin "1") (pinfunction "1_1") (pintype "unspecified"))
      (node (ref "R_A7") (pin "1") (pinfunction "1_1") (pintype "unspecified"))
      (node (ref "R_A8") (pin "1") (pinfunction "1_1") (pintype "unspecified"))
      (node (ref "R_A9") (pin "1") (pinfunction "1_1") (pintype "unspecified"))
      (node (ref "SW1") (pin "1") (pinfunction "PIN1_1") (pintype "unspecified"))
    )
    (net (code "66") (name "Net-(SW1-PIN2)") (class "Default")
      (node (ref "R_R1") (pin "1") (pinfunction "1_1") (pintype "unspecified"))
      (node (ref "R_R10") (pin "1") (pinfunction "1_1") (pintype "unspecified"))
      (node (ref "R_R11") (pin "1") (pinfunction "1_1") (pintype "unspecified"))
      (node (ref "R_R12") (pin "1") (pinfunction "1_1") (pintype "unspecified"))
      (node (ref "R_R13") (pin "1") (pinfunction "1_1") (pintype "unspecified"))
      (node (ref "R_R14") (pin "1") (pinfunction "1_1") (pintype "unspecified"))
      (node (ref "R_R15") (pin "1") (pinfunction "1_1") (pintype "unspecified"))
      (node (ref "R_R16") (pin "1") (pinfunction "1_1") (pintype "unspecified"))
      (node (ref "R_R17") (pin "1") (pinfunction "1_1") (pintype "unspecified"))
      (node (ref "R_R18") (pin "1") (pinfunction "1_1") (pintype "unspecified"))
      (node (ref "R_R19") (pin "1") (pinfunction "1_1") (pintype "unspecified"))
      (node (ref "R_R2") (pin "1") (pinfunction "1_1") (pintype "unspecified"))
      (node (ref "R_R20") (pin "1") (pinfunction "1_1") (pintype "unspecified"))
      (node (ref "R_R21") (pin "1") (pinfunction "1_1") (pintype "unspecified"))
      (node (ref "R_R22") (pin "1") (pinfunction "1_1") (pintype "unspecified"))
      (node (ref "R_R23") (pin "1") (pinfunction "1_1") (pintype "unspecified"))
      (node (ref "R_R24") (pin "1") (pinfunction "1_1") (pintype "unspecified"))
      (node (ref "R_R25") (pin "1") (pinfunction "1_1") (pintype "unspecified"))
      (node (ref "R_R26") (pin "1") (pinfunction "1_1") (pintype "unspecified"))
      (node (ref "R_R27") (pin "1") (pinfunction "1_1") (pintype "unspecified"))
      (node (ref "R_R28") (pin "1") (pinfunction "1_1") (pintype "unspecified"))
      (node (ref "R_R29") (pin "1") (pinfunction "1_1") (pintype "unspecified"))
      (node (ref "R_R3") (pin "1") (pinfunction "1_1") (pintype "unspecified"))
      (node (ref "R_R30") (pin "1") (pinfunction "1_1") (pintype "unspecified"))
      (node (ref "R_R31") (pin "1") (pinfunction "1_1") (pintype "unspecified"))
      (node (ref "R_R32") (pin "1") (pinfunction "1_1") (pintype "unspecified"))
      (node (ref "R_R4") (pin "1") (pinfunction "1_1") (pintype "unspecified"))
      (node (ref "R_R5") (pin "1") (pinfunction "1_1") (pintype "unspecified"))
      (node (ref "R_R6") (pin "1") (pinfunction "1_1") (pintype "unspecified"))
      (node (ref "R_R7") (pin "1") (pinfunction "1_1") (pintype "unspecified"))
      (node (ref "R_R8") (pin "1") (pinfunction "1_1") (pintype "unspecified"))
      (node (ref "R_R9") (pin "1") (pinfunction "1_1") (pintype "unspecified"))
      (node (ref "SW1") (pin "2") (pinfunction "PIN2_2") (pintype "unspecified"))
    )
    (net (code "67") (name "Net-(SW1-PIN3)") (class "Default")
      (node (ref "LED1") (pin "3") (pinfunction "-_3") (pintype "unspecified"))
      (node (ref "LED10") (pin "3") (pinfunction "-_3") (pintype "unspecified"))
      (node (ref "LED11") (pin "3") (pinfunction "-_3") (pintype "unspecified"))
      (node (ref "LED12") (pin "3") (pinfunction "-_3") (pintype "unspecified"))
      (node (ref "LED13") (pin "3") (pinfunction "-_3") (pintype "unspecified"))
      (node (ref "LED14") (pin "3") (pinfunction "-_3") (pintype "unspecified"))
      (node (ref "LED15") (pin "3") (pinfunction "-_3") (pintype "unspecified"))
      (node (ref "LED16") (pin "3") (pinfunction "-_3") (pintype "unspecified"))
      (node (ref "LED17") (pin "3") (pinfunction "-_3") (pintype "unspecified"))
      (node (ref "LED18") (pin "3") (pinfunction "-_3") (pintype "unspecified"))
      (node (ref "LED19") (pin "3") (pinfunction "-_3") (pintype "unspecified"))
      (node (ref "LED2") (pin "3") (pinfunction "-_3") (pintype "unspecified"))
      (node (ref "LED20") (pin "3") (pinfunction "-_3") (pintype "unspecified"))
      (node (ref "LED21") (pin "3") (pinfunction "-_3") (pintype "unspecified"))
      (node (ref "LED22") (pin "3") (pinfunction "-_3") (pintype "unspecified"))
      (node (ref "LED23") (pin "3") (pinfunction "-_3") (pintype "unspecified"))
      (node (ref "LED24") (pin "3") (pinfunction "-_3") (pintype "unspecified"))
      (node (ref "LED25") (pin "3") (pinfunction "-_3") (pintype "unspecified"))
      (node (ref "LED26") (pin "3") (pinfunction "-_3") (pintype "unspecified"))
      (node (ref "LED27") (pin "3") (pinfunction "-_3") (pintype "unspecified"))
      (node (ref "LED28") (pin "3") (pinfunction "-_3") (pintype "unspecified"))
      (node (ref "LED29") (pin "3") (pinfunction "-_3") (pintype "unspecified"))
      (node (ref "LED3") (pin "3") (pinfunction "-_3") (pintype "unspecified"))
      (node (ref "LED30") (pin "3") (pinfunction "-_3") (pintype "unspecified"))
      (node (ref "LED31") (pin "3") (pinfunction "-_3") (pintype "unspecified"))
      (node (ref "LED32") (pin "3") (pinfunction "-_3") (pintype "unspecified"))
      (node (ref "LED4") (pin "3") (pinfunction "-_3") (pintype "unspecified"))
      (node (ref "LED5") (pin "3") (pinfunction "-_3") (pintype "unspecified"))
      (node (ref "LED6") (pin "3") (pinfunction "-_3") (pintype "unspecified"))
      (node (ref "LED7") (pin "3") (pinfunction "-_3") (pintype "unspecified"))
      (node (ref "LED8") (pin "3") (pinfunction "-_3") (pintype "unspecified"))
      (node (ref "LED9") (pin "3") (pinfunction "-_3") (pintype "unspecified"))
      (node (ref "SW1") (pin "3") (pinfunction "PIN3_3") (pintype "unspecified"))
    )
    (net (code "68") (name "Net-(SW1-PIN4)") (class "Default")
      (node (ref "LED1") (pin "4") (pinfunction "-_4") (pintype "unspecified"))
      (node (ref "LED10") (pin "4") (pinfunction "-_4") (pintype "unspecified"))
      (node (ref "LED11") (pin "4") (pinfunction "-_4") (pintype "unspecified"))
      (node (ref "LED12") (pin "4") (pinfunction "-_4") (pintype "unspecified"))
      (node (ref "LED13") (pin "4") (pinfunction "-_4") (pintype "unspecified"))
      (node (ref "LED14") (pin "4") (pinfunction "-_4") (pintype "unspecified"))
      (node (ref "LED15") (pin "4") (pinfunction "-_4") (pintype "unspecified"))
      (node (ref "LED16") (pin "4") (pinfunction "-_4") (pintype "unspecified"))
      (node (ref "LED17") (pin "4") (pinfunction "-_4") (pintype "unspecified"))
      (node (ref "LED18") (pin "4") (pinfunction "-_4") (pintype "unspecified"))
      (node (ref "LED19") (pin "4") (pinfunction "-_4") (pintype "unspecified"))
      (node (ref "LED2") (pin "4") (pinfunction "-_4") (pintype "unspecified"))
      (node (ref "LED20") (pin "4") (pinfunction "-_4") (pintype "unspecified"))
      (node (ref "LED21") (pin "4") (pinfunction "-_4") (pintype "unspecified"))
      (node (ref "LED22") (pin "4") (pinfunction "-_4") (pintype "unspecified"))
      (node (ref "LED23") (pin "4") (pinfunction "-_4") (pintype "unspecified"))
      (node (ref "LED24") (pin "4") (pinfunction "-_4") (pintype "unspecified"))
      (node (ref "LED25") (pin "4") (pinfunction "-_4") (pintype "unspecified"))
      (node (ref "LED26") (pin "4") (pinfunction "-_4") (pintype "unspecified"))
      (node (ref "LED27") (pin "4") (pinfunction "-_4") (pintype "unspecified"))
      (node (ref "LED28") (pin "4") (pinfunction "-_4") (pintype "unspecified"))
      (node (ref "LED29") (pin "4") (pinfunction "-_4") (pintype "unspecified"))
      (node (ref "LED3") (pin "4") (pinfunction "-_4") (pintype "unspecified"))
      (node (ref "LED30") (pin "4") (pinfunction "-_4") (pintype "unspecified"))
      (node (ref "LED31") (pin "4") (pinfunction "-_4") (pintype "unspecified"))
      (node (ref "LED32") (pin "4") (pinfunction "-_4") (pintype "unspecified"))
      (node (ref "LED4") (pin "4") (pinfunction "-_4") (pintype "unspecified"))
      (node (ref "LED5") (pin "4") (pinfunction "-_4") (pintype "unspecified"))
      (node (ref "LED6") (pin "4") (pinfunction "-_4") (pintype "unspecified"))
      (node (ref "LED7") (pin "4") (pinfunction "-_4") (pintype "unspecified"))
      (node (ref "LED8") (pin "4") (pinfunction "-_4") (pintype "unspecified"))
      (node (ref "LED9") (pin "4") (pinfunction "-_4") (pintype "unspecified"))
      (node (ref "SW1") (pin "4") (pinfunction "PIN4_4") (pintype "unspecified"))
    )
    (net (code "69") (name "Net-(SW1-PIN5)") (class "Default")
      (node (ref "GND") (pin "1") (pinfunction "1_1") (pintype "unspecified"))
      (node (ref "SW1") (pin "5") (pinfunction "PIN5_5") (pintype "unspecified"))
      (node (ref "SW1") (pin "6") (pinfunction "PIN6_6") (pintype "unspecified"))
      (node (ref "SW1") (pin "7") (pinfunction "PIN7_7") (pintype "unspecified"))
    )
    (net (code "70") (name "Net-(SW1-PIN8)") (class "Default")
      (node (ref "SW1") (pin "8") (pinfunction "PIN8_8") (pintype "unspecified"))
      (node (ref "VCC") (pin "1") (pinfunction "1_1") (pintype "unspecified"))
    )
  )
)
